# Power.net
KiCad netlist of a schematic drawn in Altium Designer
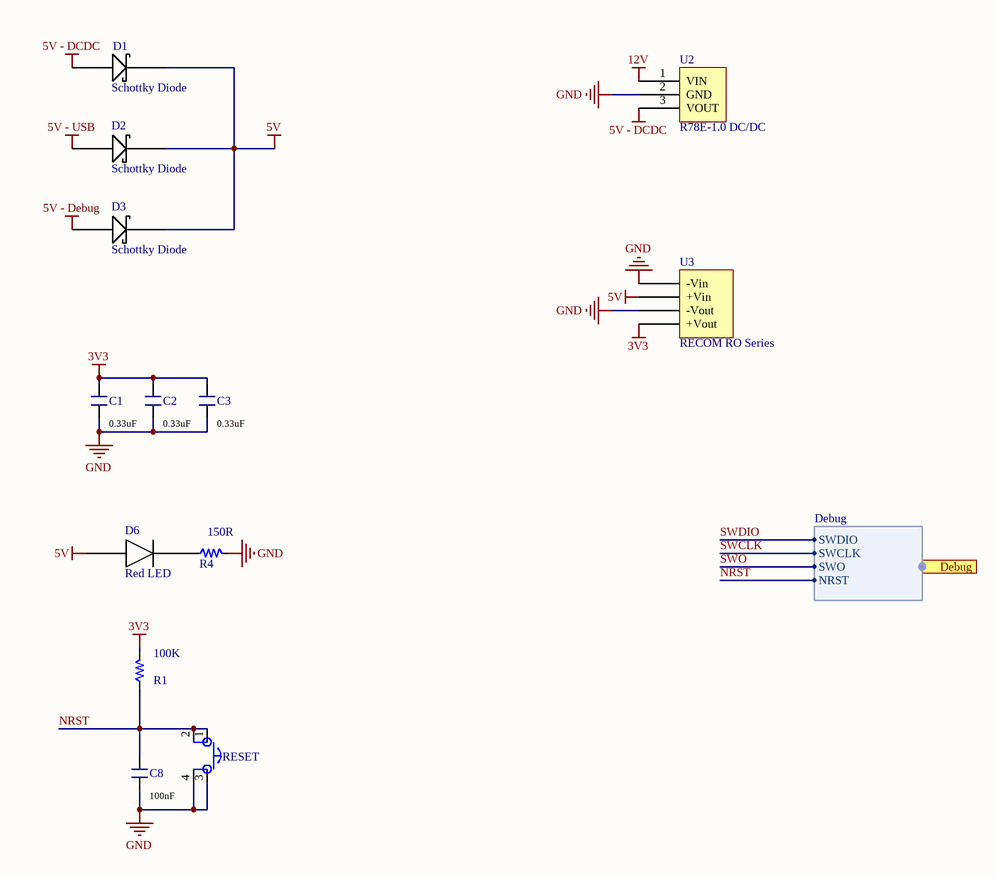
[diagram p0: Power.SchDoc]

(export (version "E")
  (design (tool "Eeschema 10.0.6"))
  (components
    (comp (ref "C1")
      (value "SCH_GENERIC_CAPACITOR_0603")
      (footprint "PCB_GENERIC_SMD_0603")
      (description "Generic SMD capacitor 0603")
      (fields (field (name "CAPACITANCE") "0.33uF"))
      (libsource (lib "Capacitors") (part "SCH_GENERIC_CAPACITOR_0603"))
    )
    (comp (ref "C2")
      (value "SCH_GENERIC_CAPACITOR_0603")
      (footprint "PCB_GENERIC_SMD_0603")
      (description "Generic SMD capacitor 0603")
      (fields (field (name "TOLERANCE") "*%") (field (name "CAPACITANCE") "0.33uF"))
      (libsource (lib "Capacitors") (part "SCH_GENERIC_CAPACITOR_0603"))
    )
    (comp (ref "C3")
      (value "SCH_GENERIC_CAPACITOR_0603")
      (footprint "PCB_GENERIC_SMD_0603")
      (description "Generic SMD capacitor 0603")
      (fields (field (name "TOLERANCE") "*%") (field (name "CAPACITANCE") "0.33uF"))
      (libsource (lib "Capacitors") (part "SCH_GENERIC_CAPACITOR_0603"))
    )
    (comp (ref "C8")
      (value "SCH_GENERIC_CAPACITOR_0603")
      (footprint "PCB_GENERIC_SMD_0603")
      (description "Generic SMD capacitor 0603")
      (fields (field (name "TOLERANCE") "*%") (field (name "CAPACITANCE") "100nF"))
      (libsource (lib "Capacitors") (part "SCH_GENERIC_CAPACITOR_0603"))
    )
    (comp (ref "D1")
      (value "Schottky Diode")
      (footprint "ON Semi Schottky Diode - MBRM110LT1G")
      (libsource (lib "ON Semi Schottky Diode - MBRM110LT1G") (part "ON Semi Schottky Diode - MBRM110LT1G"))
    )
    (comp (ref "D2")
      (value "Schottky Diode")
      (footprint "ON Semi Schottky Diode - MBRM110LT1G")
      (libsource (lib "ON Semi Schottky Diode - MBRM110LT1G") (part "ON Semi Schottky Diode - MBRM110LT1G"))
    )
    (comp (ref "D3")
      (value "Schottky Diode")
      (footprint "ON Semi Schottky Diode - MBRM110LT1G")
      (libsource (lib "ON Semi Schottky Diode - MBRM110LT1G") (part "ON Semi Schottky Diode - MBRM110LT1G"))
    )
    (comp (ref "D6")
      (value "Red LED")
      (footprint "SMD_0603_LED")
      (libsource (lib "SMD_0603_LED") (part "SMD_0603_LED"))
    )
    (comp (ref "R1")
      (value "SCH_GENERIC_RESISTOR_0603")
      (footprint "PCB_GENERIC_SMD_0603")
      (description "Generic SMD resistor 0603")
      (fields (field (name "RESISTANCE") "100K"))
      (libsource (lib "Resistors") (part "SCH_GENERIC_RESISTOR_0603"))
    )
    (comp (ref "R4")
      (value "SCH_GENERIC_RESISTOR_0603")
      (footprint "PCB_GENERIC_SMD_0603")
      (description "Generic SMD resistor 0603")
      (fields (field (name "RESISTANCE") "150R"))
      (libsource (lib "SCH_GENERIC_RESISTOR_0603") (part "SCH_GENERIC_RESISTOR_0603"))
    )
    (comp (ref "RESET")
      (value "Tactile Switch")
      (footprint "C&K 4 pin Tactile Switch")
      (libsource (lib "C&K 4 Pin Tactile Switch") (part "C&K Tactile Switch"))
    )
    (comp (ref "U2")
      (value "R78E-1.0 DC/DC")
      (footprint "R78-1.0")
      (libsource (lib "R78E-1.0_DCDC_SCH") (part "R78E-1.0"))
    )
    (comp (ref "U3")
      (value "RECOM RO Series")
      (footprint "RECOM RO Series 1W DCDC")
      (libsource (lib "RECOM RO Series 1W DCDC") (part "RECOM RO Series DCDC Converter"))
    )
  )
  (nets
    (net (code "2") (name "/NRST") (class "Default")
      (node (ref "C8") (pin "1") (pinfunction "1_1") (pintype "passive"))
      (node (ref "R1") (pin "1") (pinfunction "1_1") (pintype "passive"))
      (node (ref "RESET") (pin "1") (pinfunction "1_1") (pintype "passive"))
      (node (ref "RESET") (pin "2") (pinfunction "2_2") (pintype "passive"))
    )
    (net (code "7") (name "3V3") (class "Default")
      (node (ref "C1") (pin "2") (pinfunction "2_2") (pintype "passive"))
      (node (ref "C2") (pin "2") (pinfunction "2_2") (pintype "passive"))
      (node (ref "C3") (pin "2") (pinfunction "2_2") (pintype "passive"))
      (node (ref "R1") (pin "2") (pinfunction "2_2") (pintype "passive"))
      (node (ref "U3") (pin "4") (pinfunction "+Vout_4") (pintype "passive"))
    )
    (net (code "8") (name "5V") (class "Default")
      (node (ref "D1") (pin "1") (pinfunction "1_1") (pintype "passive"))
      (node (ref "D2") (pin "1") (pinfunction "1_1") (pintype "passive"))
      (node (ref "D3") (pin "1") (pinfunction "1_1") (pintype "passive"))
      (node (ref "D6") (pin "1") (pinfunction "1_1") (pintype "passive"))
      (node (ref "U3") (pin "2") (pinfunction "+Vin_2") (pintype "passive"))
    )
    (net (code "9") (name "5V - DCDC") (class "Default")
      (node (ref "D1") (pin "2") (pinfunction "2_2") (pintype "passive"))
      (node (ref "U2") (pin "3") (pinfunction "VOUT_3") (pintype "passive"))
    )
    (net (code "10") (name "5V - Debug") (class "Default")
      (node (ref "D3") (pin "2") (pinfunction "2_2") (pintype "passive"))
    )
    (net (code "11") (name "5V - USB") (class "Default")
      (node (ref "D2") (pin "2") (pinfunction "2_2") (pintype "passive"))
    )
    (net (code "12") (name "12V") (class "Default")
      (node (ref "U2") (pin "1") (pinfunction "VIN_1") (pintype "passive"))
    )
    (net (code "13") (name "GND") (class "Default")
      (node (ref "C1") (pin "1") (pinfunction "1_1") (pintype "passive"))
      (node (ref "C2") (pin "1") (pinfunction "1_1") (pintype "passive"))
      (node (ref "C3") (pin "1") (pinfunction "1_1") (pintype "passive"))
      (node (ref "C8") (pin "2") (pinfunction "2_2") (pintype "passive"))
      (node (ref "R4") (pin "2") (pinfunction "2_2") (pintype "passive"))
      (node (ref "RESET") (pin "3") (pinfunction "3_3") (pintype "passive"))
      (node (ref "RESET") (pin "4") (pinfunction "4_4") (pintype "passive"))
      (node (ref "U2") (pin "2") (pinfunction "GND_2") (pintype "passive"))
      (node (ref "U3") (pin "1") (pinfunction "-Vin_1") (pintype "passive"))
      (node (ref "U3") (pin "3") (pinfunction "-Vout_3") (pintype "passive"))
    )
    (net (code "14") (name "Net-(D6-Pad2)") (class "Default")
      (node (ref "D6") (pin "2") (pinfunction "2_2") (pintype "passive"))
      (node (ref "R4") (pin "1") (pinfunction "1_1") (pintype "passive"))
    )
  )
)
